# MyDeskThingy.net
KiCad netlist of a schematic drawn in EasyEDA Pro
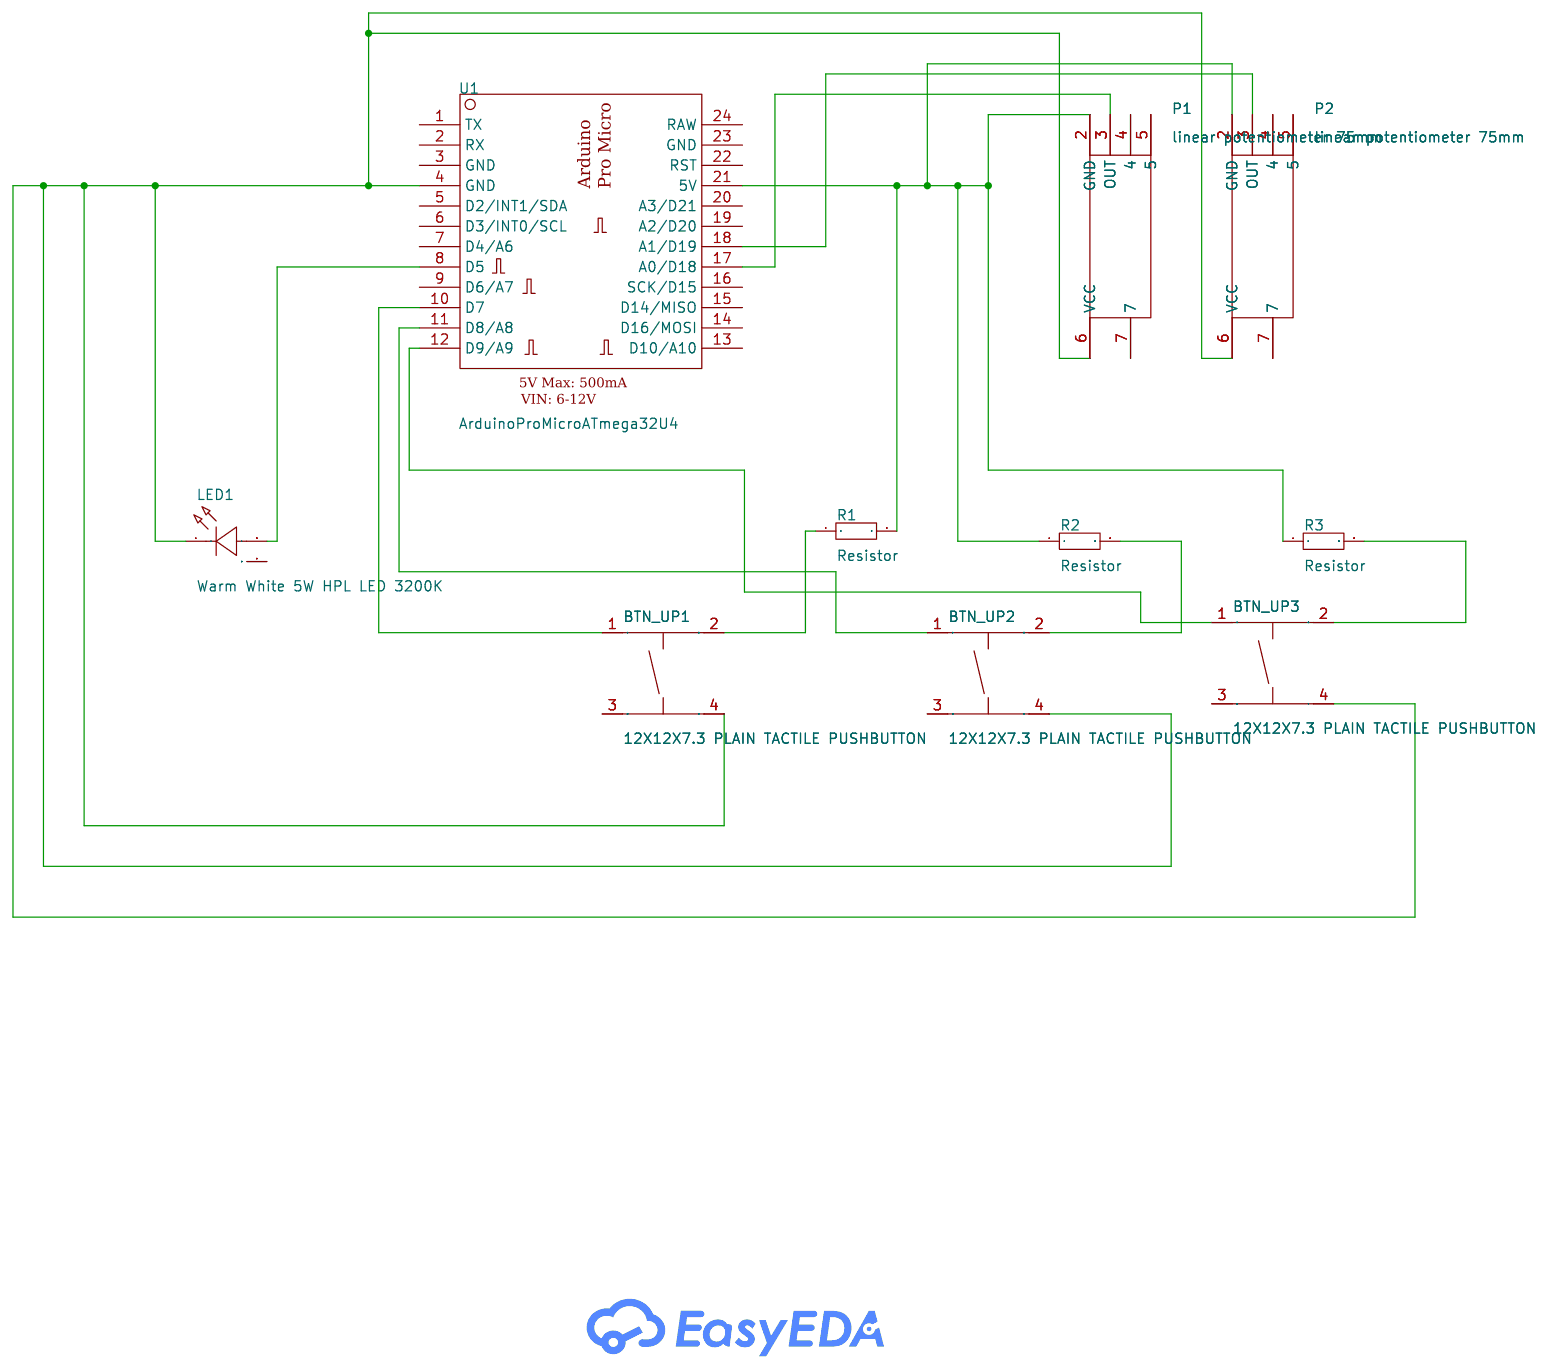
[diagram p0: schematic sheet]

(export (version "E")
  (design (tool "Eeschema 10.0.6"))
  (components
    (comp (ref "BTN_UP1")
      (value "12X12X7.3 PLAIN TACTILE PUSHBUTTON")
      (footprint "easyedapro:SW-TH_4P-L12.0-W12.0-P5.00-LS12.5")
      (fields (field (name "Manufacturer") "Boom Precision Elec"))
      (libsource (lib "easyedapro") (part "12X12X7.3 PLAIN TACTILE PUSHBUTTON"))
    )
    (comp (ref "BTN_UP2")
      (value "12X12X7.3 PLAIN TACTILE PUSHBUTTON")
      (footprint "easyedapro:SW-TH_4P-L12.0-W12.0-P5.00-LS12.5")
      (fields (field (name "Manufacturer") "Boom Precision Elec"))
      (libsource (lib "easyedapro") (part "12X12X7.3 PLAIN TACTILE PUSHBUTTON"))
    )
    (comp (ref "BTN_UP3")
      (value "12X12X7.3 PLAIN TACTILE PUSHBUTTON")
      (footprint "easyedapro:SW-TH_4P-L12.0-W12.0-P5.00-LS12.5")
      (fields (field (name "Manufacturer") "Boom Precision Elec"))
      (libsource (lib "easyedapro") (part "12X12X7.3 PLAIN TACTILE PUSHBUTTON"))
    )
    (comp (ref "LED1")
      (value "Warm White 5W HPL LED 3200K")
      (footprint "easyedapro:LED-SMD_HL-EF45W1NAMS_BIG")
      (description "2500K - 3500K, 6-7V, 600-700mA, Lumen 450-500 LM")
      (fields (field (name "Manufacturer") "LCFOCUS"))
      (libsource (lib "easyedapro") (part "LC-5WW-C45"))
    )
    (comp (ref "P1")
      (value "linear potentiometer 75mm")
      (footprint "easyedapro:MY Slide Pot 75mm")
      (libsource (lib "easyedapro") (part "Slide Pot 75mm"))
    )
    (comp (ref "P2")
      (value "linear potentiometer 75mm")
      (footprint "easyedapro:MY Slide Pot 75mm")
      (libsource (lib "easyedapro") (part "Slide Pot 75mm"))
    )
    (comp (ref "R1")
      (value "Resistor")
      (footprint "easyedapro:Resistor 1/8w 7mm metal film")
      (fields
        (field (name "Manufacturer Part") "1206W4F1002T5E")
        (field (name "Manufacturer") "UNI-ROYAL(Uniroyal Elec)")
      )
      (libsource (lib "easyedapro") (part "resistor"))
    )
    (comp (ref "R2")
      (value "Resistor")
      (footprint "easyedapro:Resistor 1/8w 7mm metal film")
      (fields
        (field (name "Manufacturer Part") "1206W4F1002T5E")
        (field (name "Manufacturer") "UNI-ROYAL(Uniroyal Elec)")
      )
      (libsource (lib "easyedapro") (part "resistor"))
    )
    (comp (ref "R3")
      (value "Resistor")
      (footprint "easyedapro:Resistor 1/8w 7mm metal film")
      (fields
        (field (name "Manufacturer Part") "1206W4F1002T5E")
        (field (name "Manufacturer") "UNI-ROYAL(Uniroyal Elec)")
      )
      (libsource (lib "easyedapro") (part "resistor"))
    )
    (comp (ref "U1")
      (value "ArduinoProMicroATmega32U4")
      (footprint "easyedapro:ARDUINOPROMICRO")
      (libsource (lib "easyedapro") (part "ArduinoProMicroATmega32U4"))
    )
  )
  (nets
    (net (code "1") (name "Net-(BTN_UP1-Pad2)") (class "Default")
      (node (ref "BTN_UP1") (pin "2") (pinfunction "2_2") (pintype "unspecified"))
      (node (ref "R1") (pin "1") (pinfunction "1_1") (pintype "input"))
    )
    (net (code "2") (name "Net-(BTN_UP2-Pad2)") (class "Default")
      (node (ref "BTN_UP2") (pin "2") (pinfunction "2_2") (pintype "unspecified"))
      (node (ref "R2") (pin "2") (pinfunction "2_2") (pintype "input"))
    )
    (net (code "3") (name "Net-(BTN_UP3-Pad2)") (class "Default")
      (node (ref "BTN_UP3") (pin "2") (pinfunction "2_2") (pintype "unspecified"))
      (node (ref "R3") (pin "2") (pinfunction "2_2") (pintype "input"))
    )
    (net (code "4") (name "Net-(LED1-A)") (class "Default")
      (node (ref "LED1") (pin "2") (pinfunction "A_2") (pintype "input"))
      (node (ref "U1") (pin "8") (pinfunction "D5_8") (pintype "input"))
    )
    (net (code "5") (name "Net-(LED1-K)") (class "Default")
      (node (ref "BTN_UP1") (pin "4") (pinfunction "4_4") (pintype "unspecified"))
      (node (ref "BTN_UP2") (pin "4") (pinfunction "4_4") (pintype "unspecified"))
      (node (ref "BTN_UP3") (pin "4") (pinfunction "4_4") (pintype "unspecified"))
      (node (ref "LED1") (pin "1") (pinfunction "K_1") (pintype "input"))
      (node (ref "P1") (pin "6") (pinfunction "VCC_6") (pintype "input"))
      (node (ref "P2") (pin "6") (pinfunction "VCC_6") (pintype "input"))
      (node (ref "U1") (pin "4") (pinfunction "GND_4") (pintype "input"))
    )
    (net (code "6") (name "Net-(P1-GND)") (class "Default")
      (node (ref "P1") (pin "2") (pinfunction "GND_2") (pintype "input"))
      (node (ref "P2") (pin "2") (pinfunction "GND_2") (pintype "input"))
      (node (ref "R1") (pin "2") (pinfunction "2_2") (pintype "input"))
      (node (ref "R2") (pin "1") (pinfunction "1_1") (pintype "input"))
      (node (ref "R3") (pin "1") (pinfunction "1_1") (pintype "input"))
      (node (ref "U1") (pin "21") (pinfunction "5V_21") (pintype "input"))
    )
    (net (code "7") (name "Net-(P1-OUT)") (class "Default")
      (node (ref "P1") (pin "3") (pinfunction "OUT_3") (pintype "input"))
      (node (ref "U1") (pin "17") (pinfunction "A0/D18_17") (pintype "input"))
    )
    (net (code "8") (name "Net-(P2-OUT)") (class "Default")
      (node (ref "P2") (pin "3") (pinfunction "OUT_3") (pintype "input"))
      (node (ref "U1") (pin "18") (pinfunction "A1/D19_18") (pintype "input"))
    )
    (net (code "9") (name "Net-(U1-D7)") (class "Default")
      (node (ref "BTN_UP1") (pin "1") (pinfunction "1_1") (pintype "unspecified"))
      (node (ref "U1") (pin "10") (pinfunction "D7_10") (pintype "input"))
    )
    (net (code "10") (name "Net-(U1-D8{slash}A8)") (class "Default")
      (node (ref "BTN_UP2") (pin "1") (pinfunction "1_1") (pintype "unspecified"))
      (node (ref "U1") (pin "11") (pinfunction "D8/A8_11") (pintype "input"))
    )
    (net (code "11") (name "Net-(U1-D9{slash}A9)") (class "Default")
      (node (ref "BTN_UP3") (pin "1") (pinfunction "1_1") (pintype "unspecified"))
      (node (ref "U1") (pin "12") (pinfunction "D9/A9_12") (pintype "input"))
    )
    (net (code "12") (name "unconnected-(BTN_UP1-Pad3)") (class "Default")
      (node (ref "BTN_UP1") (pin "3") (pinfunction "3_3") (pintype "unspecified"))
    )
    (net (code "13") (name "unconnected-(BTN_UP2-Pad3)") (class "Default")
      (node (ref "BTN_UP2") (pin "3") (pinfunction "3_3") (pintype "unspecified"))
    )
    (net (code "14") (name "unconnected-(BTN_UP3-Pad3)") (class "Default")
      (node (ref "BTN_UP3") (pin "3") (pinfunction "3_3") (pintype "unspecified"))
    )
    (net (code "15") (name "unconnected-(LED1-Pad3)") (class "Default")
      (node (ref "LED1") (pin "3") (pinfunction "3_3") (pintype "input"))
    )
    (net (code "16") (name "unconnected-(P1-Pad4)") (class "Default")
      (node (ref "P1") (pin "4") (pinfunction "4_4") (pintype "input"))
    )
    (net (code "17") (name "unconnected-(P1-Pad5)") (class "Default")
      (node (ref "P1") (pin "5") (pinfunction "5_5") (pintype "input"))
    )
    (net (code "18") (name "unconnected-(P1-Pad7)") (class "Default")
      (node (ref "P1") (pin "7") (pinfunction "7_7") (pintype "input"))
    )
    (net (code "19") (name "unconnected-(P2-Pad4)") (class "Default")
      (node (ref "P2") (pin "4") (pinfunction "4_4") (pintype "input"))
    )
    (net (code "20") (name "unconnected-(P2-Pad5)") (class "Default")
      (node (ref "P2") (pin "5") (pinfunction "5_5") (pintype "input"))
    )
    (net (code "21") (name "unconnected-(P2-Pad7)") (class "Default")
      (node (ref "P2") (pin "7") (pinfunction "7_7") (pintype "input"))
    )
    (net (code "22") (name "unconnected-(U1-A2{slash}D20-Pad19)") (class "Default")
      (node (ref "U1") (pin "19") (pinfunction "A2/D20_19") (pintype "input"))
    )
    (net (code "23") (name "unconnected-(U1-A3{slash}D21-Pad20)") (class "Default")
      (node (ref "U1") (pin "20") (pinfunction "A3/D21_20") (pintype "input"))
    )
    (net (code "24") (name "unconnected-(U1-D2{slash}INT1{slash}SDA-Pad5)") (class "Default")
      (node (ref "U1") (pin "5") (pinfunction "D2/INT1/SDA_5") (pintype "input"))
    )
    (net (code "25") (name "unconnected-(U1-D3{slash}INT0{slash}SCL-Pad6)") (class "Default")
      (node (ref "U1") (pin "6") (pinfunction "D3/INT0/SCL_6") (pintype "input"))
    )
    (net (code "26") (name "unconnected-(U1-D4{slash}A6-Pad7)") (class "Default")
      (node (ref "U1") (pin "7") (pinfunction "D4/A6_7") (pintype "input"))
    )
    (net (code "27") (name "unconnected-(U1-D6{slash}A7-Pad9)") (class "Default")
      (node (ref "U1") (pin "9") (pinfunction "D6/A7_9") (pintype "input"))
    )
    (net (code "28") (name "unconnected-(U1-D10{slash}A10-Pad13)") (class "Default")
      (node (ref "U1") (pin "13") (pinfunction "D10/A10_13") (pintype "input"))
    )
    (net (code "29") (name "unconnected-(U1-D14{slash}MISO-Pad15)") (class "Default")
      (node (ref "U1") (pin "15") (pinfunction "D14/MISO_15") (pintype "input"))
    )
    (net (code "30") (name "unconnected-(U1-D16{slash}MOSI-Pad14)") (class "Default")
      (node (ref "U1") (pin "14") (pinfunction "D16/MOSI_14") (pintype "input"))
    )
    (net (code "31") (name "unconnected-(U1-GND-Pad3)") (class "Default")
      (node (ref "U1") (pin "3") (pinfunction "GND_3") (pintype "input"))
    )
    (net (code "32") (name "unconnected-(U1-GND-Pad23)") (class "Default")
      (node (ref "U1") (pin "23") (pinfunction "GND_23") (pintype "input"))
    )
    (net (code "33") (name "unconnected-(U1-RAW-Pad24)") (class "Default")
      (node (ref "U1") (pin "24") (pinfunction "RAW_24") (pintype "input"))
    )
    (net (code "34") (name "unconnected-(U1-RST-Pad22)") (class "Default")
      (node (ref "U1") (pin "22") (pinfunction "RST_22") (pintype "input"))
    )
    (net (code "35") (name "unconnected-(U1-RX-Pad2)") (class "Default")
      (node (ref "U1") (pin "2") (pinfunction "RX_2") (pintype "input"))
    )
    (net (code "36") (name "unconnected-(U1-SCK{slash}D15-Pad16)") (class "Default")
      (node (ref "U1") (pin "16") (pinfunction "SCK/D15_16") (pintype "input"))
    )
    (net (code "37") (name "unconnected-(U1-TX-Pad1)") (class "Default")
      (node (ref "U1") (pin "1") (pinfunction "TX_1") (pintype "input"))
    )
  )
)
